# GSM_Modem_Antenna.net
KiCad netlist of a schematic drawn in Altium Designer
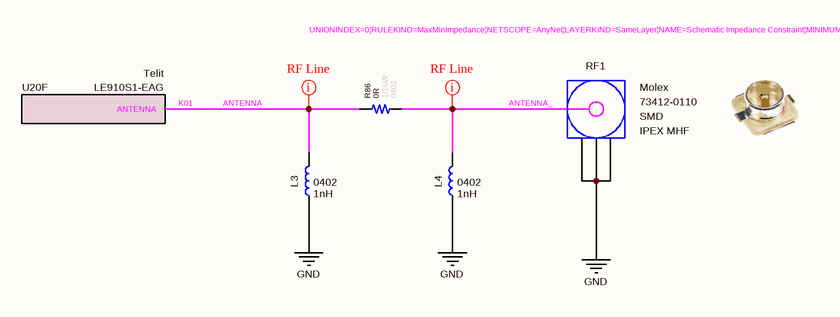
[diagram p0: GSM Modem Antenna.SchDoc]

(export (version "E")
  (design (tool "Eeschema 10.0.6"))
  (components
    (comp (ref "L3")
      (value "1nH")
      (footprint "INDUCTOR_0402")
      (description "Fixed Inductor")
      (fields
        (field (name "MANUFACTURER PART NUMBER") "LQG15HN1N0S02D")
        (field (name "TOLERANCE") "0.3 nH")
        (field (name "CASE") "0402")
      )
      (libsource (lib "Akkoyun") (part "Inductor - 1nH [0402]"))
    )
    (comp (ref "L4")
      (value "1nH")
      (footprint "INDUCTOR_0402")
      (description "Fixed Inductor")
      (fields
        (field (name "MANUFACTURER PART NUMBER") "LQG15HN1N0S02D")
        (field (name "TOLERANCE") "0.3 nH")
        (field (name "CASE") "0402")
      )
      (libsource (lib "Akkoyun") (part "Inductor - 1nH [0402]"))
    )
    (comp (ref "R86")
      (value "0R")
      (footprint "RESISTOR_0402")
      (description "Thick Film Resistors - SMD 1/16 W 0 Ohm")
      (fields
        (field (name "MANUFACTURER PART NUMBER") "CRCW04020000Z0ED")
        (field (name "CASE") "0402")
        (field (name "POWER") "1/16W")
        (field (name "Comment") "0R - 0402 - %1 - 1/16W")
      )
      (libsource (lib "Akkoyun") (part "Resistor - 0R [0402]"))
    )
    (comp (ref "RF1")
      (value "73412-0110")
      (footprint "Connector_IPEX")
      (description "MOLEX   73412-0110   RF COAXIAL, MICROCOAXIAL, JACK, 50OHM")
      (fields
        (field (name "CONNECTOR TYPE") "IPEX MHF")
        (field (name "CASE") "SMD")
        (field (name "MANUFACTURER PART NUMBER") "73412-0110")
        (field (name "MANUFACTURER NAME") "Molex")
      )
      (libsource (lib "Akkoyun") (part "Connector - IPEX MHF"))
    )
    (comp (ref "U20")
      (value "LE910S1-EAG LTE GSM Module")
      (footprint "LE910 GSM Modem")
      (description "Telit LE910S1-EAG GPRS/GNSS Module")
      (fields
        (field (name "MANUFACTURER PART NUMBER") "LE910S1-EAG")
        (field (name "MANUFACTURER NAME") "Telit")
      )
      (libsource (lib "Akkoyun") (part "IC - LE910S1-EAG"))
    )
  )
  (nets
    (net (code "1") (name "/ANTENNA") (class "Default")
      (node (ref "L3") (pin "2") (pinfunction "2_2") (pintype "passive"))
      (node (ref "R86") (pin "2") (pinfunction "2_2") (pintype "passive"))
      (node (ref "U20") (pin "K01") (pinfunction "ANTENNA_K01") (pintype "passive"))
    )
    (net (code "2") (name "/ANTENNA_") (class "Default")
      (node (ref "L4") (pin "2") (pinfunction "2_2") (pintype "passive"))
      (node (ref "R86") (pin "1") (pinfunction "1_1") (pintype "passive"))
      (node (ref "RF1") (pin "1") (pinfunction "Signal_1") (pintype "passive"))
    )
    (net (code "3") (name "GND") (class "Default")
      (node (ref "L3") (pin "1") (pinfunction "1_1") (pintype "passive"))
      (node (ref "L4") (pin "1") (pinfunction "1_1") (pintype "passive"))
      (node (ref "RF1") (pin "2") (pinfunction "GND_2") (pintype "passive"))
      (node (ref "RF1") (pin "3") (pinfunction "GND_3") (pintype "passive"))
      (node (ref "RF1") (pin "4") (pinfunction "GND_4") (pintype "passive"))
    )
  )
)
